# BUS2BUS_1.net
KiCad netlist of a schematic drawn in EAGLE
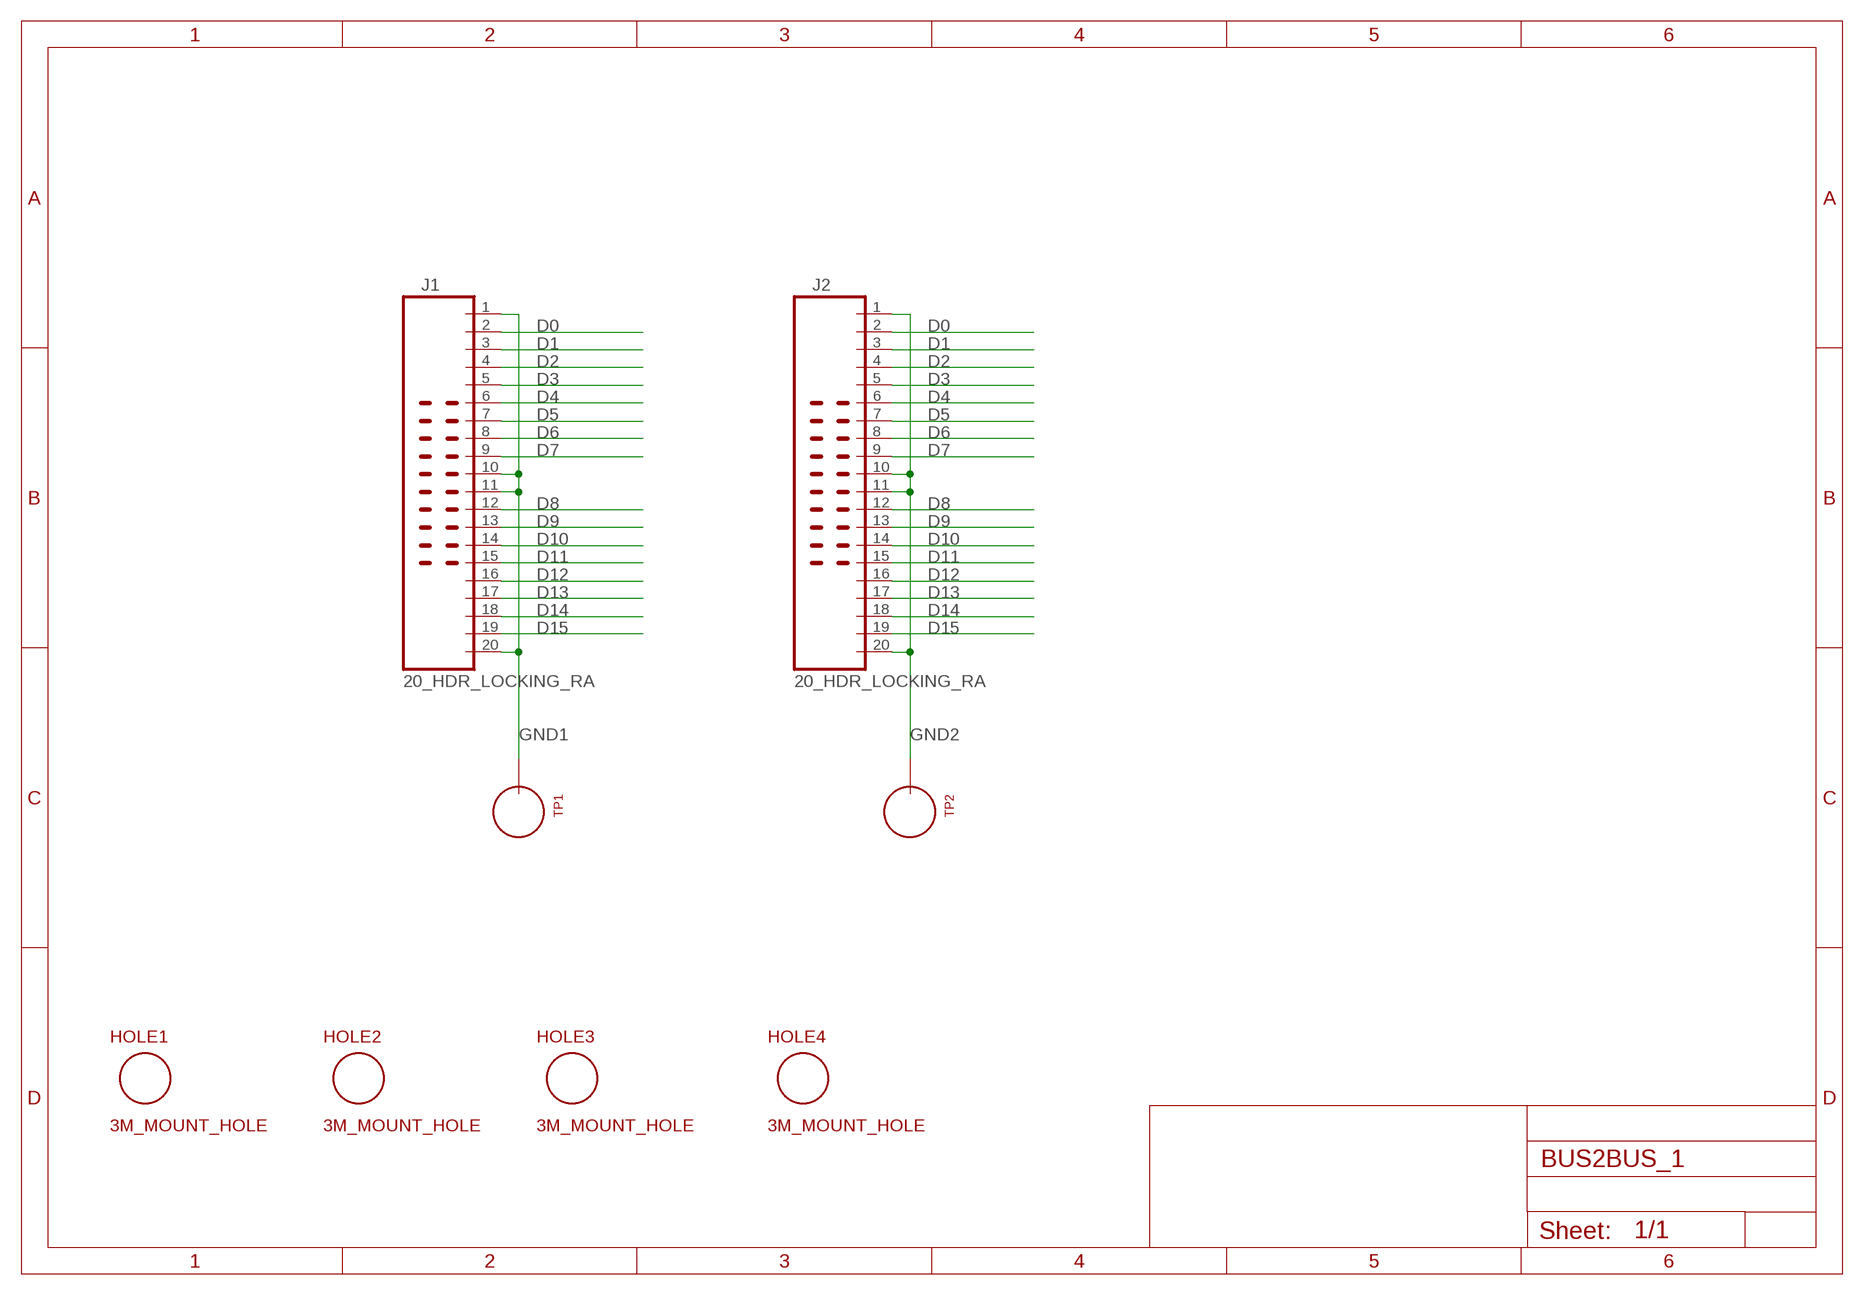
[diagram p0: schematic, sheet 1]

(export (version "E")
  (design (tool "Eeschema 10.0.6"))
  (components
    (comp (ref "HOLE1")
      (value "3M_MOUNT_HOLE")
      (footprint "eagle-import:3M_HOLE")
      (libsource (lib "eagle-import") (part "3M_MOUNT_HOLE"))
    )
    (comp (ref "HOLE2")
      (value "3M_MOUNT_HOLE")
      (footprint "eagle-import:3M_HOLE")
      (libsource (lib "eagle-import") (part "3M_MOUNT_HOLE"))
    )
    (comp (ref "HOLE3")
      (value "3M_MOUNT_HOLE")
      (footprint "eagle-import:3M_HOLE")
      (libsource (lib "eagle-import") (part "3M_MOUNT_HOLE"))
    )
    (comp (ref "HOLE4")
      (value "3M_MOUNT_HOLE")
      (footprint "eagle-import:3M_HOLE")
      (libsource (lib "eagle-import") (part "3M_MOUNT_HOLE"))
    )
    (comp (ref "J1")
      (value "20_HDR_LOCKING_RA")
      (footprint "eagle-import:20_HDR_LOCKING_RA")
      (libsource (lib "eagle-import") (part "20_HDR_LOCKING_RA"))
    )
    (comp (ref "J2")
      (value "20_HDR_LOCKING_RA")
      (footprint "eagle-import:20_HDR_LOCKING_RA")
      (libsource (lib "eagle-import") (part "20_HDR_LOCKING_RA"))
    )
    (comp (ref "TP1")
      (value "TEST_LOOP")
      (footprint "eagle-import:TEST_LOOP")
      (libsource (lib "eagle-import") (part "TEST_LOOP"))
    )
    (comp (ref "TP2")
      (value "TEST_LOOP")
      (footprint "eagle-import:TEST_LOOP")
      (libsource (lib "eagle-import") (part "TEST_LOOP"))
    )
  )
  (nets
    (net (code "1") (name "/D0") (class "Default")
      (node (ref "J1") (pin "2") (pinfunction "2_2") (pintype "bidirectional"))
      (node (ref "J2") (pin "2") (pinfunction "2_2") (pintype "bidirectional"))
    )
    (net (code "2") (name "/D1") (class "Default")
      (node (ref "J1") (pin "3") (pinfunction "3_3") (pintype "bidirectional"))
      (node (ref "J2") (pin "3") (pinfunction "3_3") (pintype "bidirectional"))
    )
    (net (code "3") (name "/D2") (class "Default")
      (node (ref "J1") (pin "4") (pinfunction "4_4") (pintype "bidirectional"))
      (node (ref "J2") (pin "4") (pinfunction "4_4") (pintype "bidirectional"))
    )
    (net (code "4") (name "/D3") (class "Default")
      (node (ref "J1") (pin "5") (pinfunction "5_5") (pintype "bidirectional"))
      (node (ref "J2") (pin "5") (pinfunction "5_5") (pintype "bidirectional"))
    )
    (net (code "5") (name "/D4") (class "Default")
      (node (ref "J1") (pin "6") (pinfunction "6_6") (pintype "bidirectional"))
      (node (ref "J2") (pin "6") (pinfunction "6_6") (pintype "bidirectional"))
    )
    (net (code "6") (name "/D5") (class "Default")
      (node (ref "J1") (pin "7") (pinfunction "7_7") (pintype "bidirectional"))
      (node (ref "J2") (pin "7") (pinfunction "7_7") (pintype "bidirectional"))
    )
    (net (code "7") (name "/D6") (class "Default")
      (node (ref "J1") (pin "8") (pinfunction "8_8") (pintype "bidirectional"))
      (node (ref "J2") (pin "8") (pinfunction "8_8") (pintype "bidirectional"))
    )
    (net (code "8") (name "/D7") (class "Default")
      (node (ref "J1") (pin "9") (pinfunction "9_9") (pintype "bidirectional"))
      (node (ref "J2") (pin "9") (pinfunction "9_9") (pintype "bidirectional"))
    )
    (net (code "9") (name "/D8") (class "Default")
      (node (ref "J1") (pin "12") (pinfunction "12_12") (pintype "bidirectional"))
      (node (ref "J2") (pin "12") (pinfunction "12_12") (pintype "bidirectional"))
    )
    (net (code "10") (name "/D9") (class "Default")
      (node (ref "J1") (pin "13") (pinfunction "13_13") (pintype "bidirectional"))
      (node (ref "J2") (pin "13") (pinfunction "13_13") (pintype "bidirectional"))
    )
    (net (code "11") (name "/D10") (class "Default")
      (node (ref "J1") (pin "14") (pinfunction "14_14") (pintype "bidirectional"))
      (node (ref "J2") (pin "14") (pinfunction "14_14") (pintype "bidirectional"))
    )
    (net (code "12") (name "/D11") (class "Default")
      (node (ref "J1") (pin "15") (pinfunction "15_15") (pintype "bidirectional"))
      (node (ref "J2") (pin "15") (pinfunction "15_15") (pintype "bidirectional"))
    )
    (net (code "13") (name "/D12") (class "Default")
      (node (ref "J1") (pin "16") (pinfunction "16_16") (pintype "bidirectional"))
      (node (ref "J2") (pin "16") (pinfunction "16_16") (pintype "bidirectional"))
    )
    (net (code "14") (name "/D13") (class "Default")
      (node (ref "J1") (pin "17") (pinfunction "17_17") (pintype "bidirectional"))
      (node (ref "J2") (pin "17") (pinfunction "17_17") (pintype "bidirectional"))
    )
    (net (code "15") (name "/D14") (class "Default")
      (node (ref "J1") (pin "18") (pinfunction "18_18") (pintype "bidirectional"))
      (node (ref "J2") (pin "18") (pinfunction "18_18") (pintype "bidirectional"))
    )
    (net (code "16") (name "/D15") (class "Default")
      (node (ref "J1") (pin "19") (pinfunction "19_19") (pintype "bidirectional"))
      (node (ref "J2") (pin "19") (pinfunction "19_19") (pintype "bidirectional"))
    )
    (net (code "17") (name "/GND1") (class "Default")
      (node (ref "J1") (pin "1") (pinfunction "1_1") (pintype "bidirectional"))
      (node (ref "J1") (pin "10") (pinfunction "10_10") (pintype "bidirectional"))
      (node (ref "J1") (pin "11") (pinfunction "11_11") (pintype "bidirectional"))
      (node (ref "J1") (pin "20") (pinfunction "20_20") (pintype "bidirectional"))
      (node (ref "TP1") (pin "P$1") (pinfunction "P$1_P$1") (pintype "bidirectional"))
    )
    (net (code "18") (name "/GND2") (class "Default")
      (node (ref "J2") (pin "1") (pinfunction "1_1") (pintype "bidirectional"))
      (node (ref "J2") (pin "10") (pinfunction "10_10") (pintype "bidirectional"))
      (node (ref "J2") (pin "11") (pinfunction "11_11") (pintype "bidirectional"))
      (node (ref "J2") (pin "20") (pinfunction "20_20") (pintype "bidirectional"))
      (node (ref "TP2") (pin "P$1") (pinfunction "P$1_P$1") (pintype "bidirectional"))
    )
  )
)
